# MicroController.net
KiCad netlist of a schematic drawn in Altium Designer
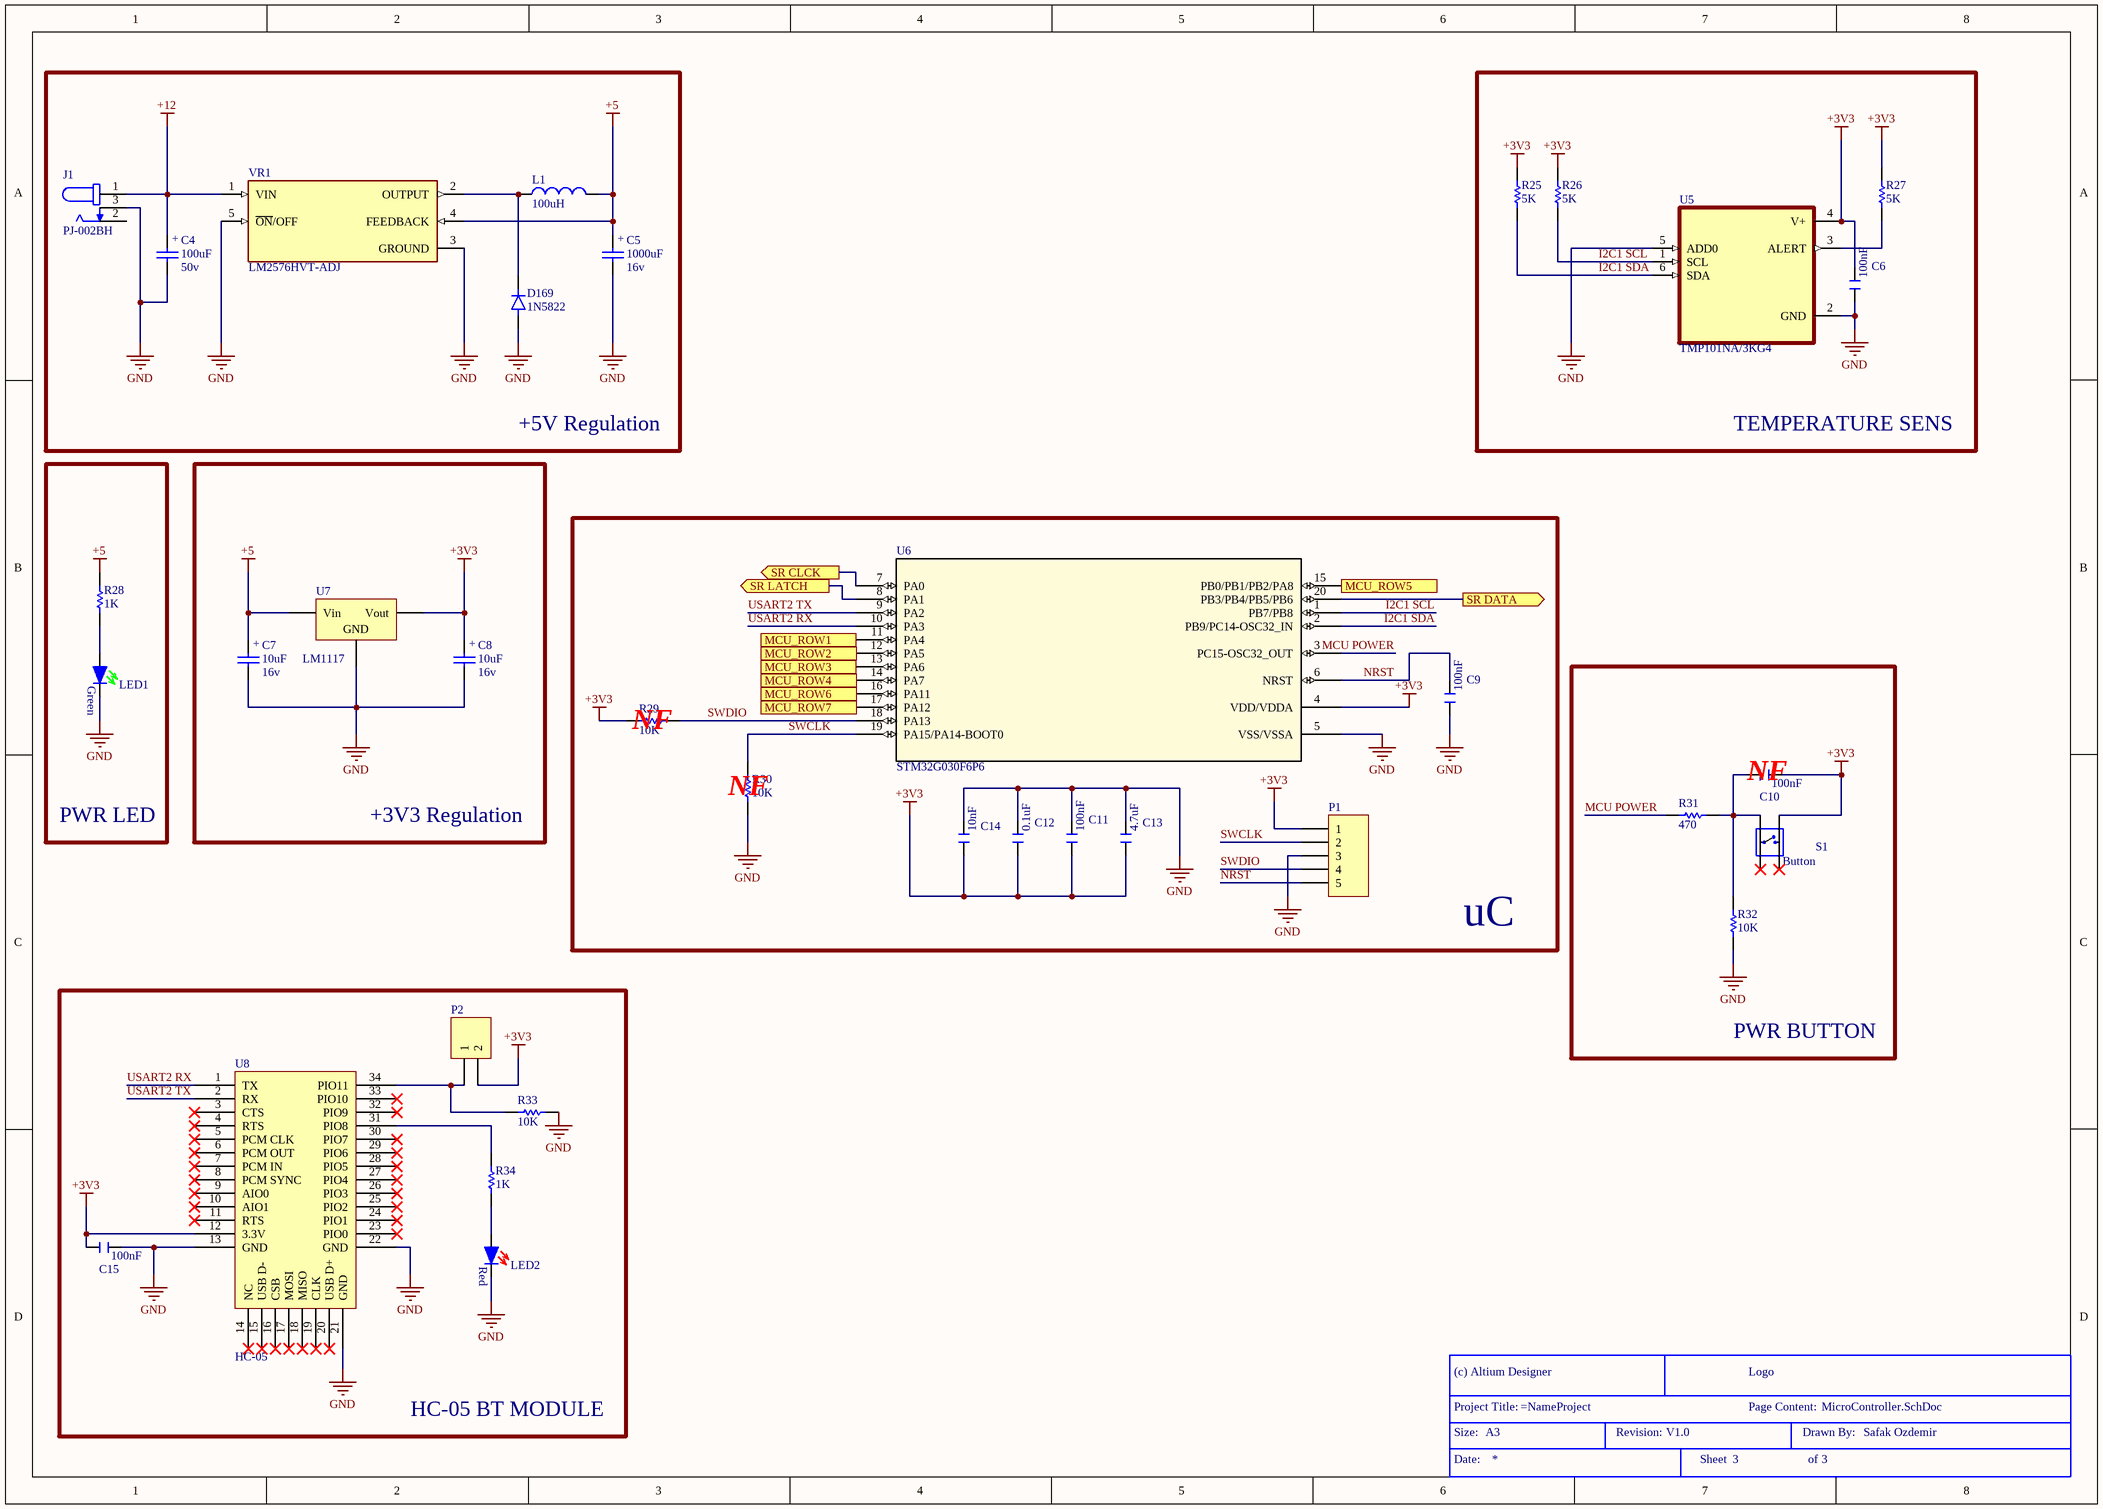
[diagram p0: MicroController.SchDoc]

(export (version "E")
  (design (tool "Eeschema 10.0.6"))
  (components
    (comp (ref "*")
      (value "Title Block")
      (fields (field (name "SIZE") "A3"))
      (libsource (lib "Bluetooth_Controlled_Led_Matrix_Design") (part "Title Block"))
    )
    (comp (ref "C4")
      (value "100uF")
      (footprint "MY_CLV_0810")
      (description "Polar capacitor")
      (fields (field (name "ASID PART NUMBER") "C-AS") (field (name "VOLTE") "50v"))
      (libsource (lib "Mylib") (part "Cap Pol"))
    )
    (comp (ref "C5")
      (value "1000uF")
      (footprint "MY_CLV_0810")
      (description "Polar capacitor")
      (fields (field (name "ASID PART NUMBER") "C-AS") (field (name "VOLTE") "16v"))
      (libsource (lib "Mylib") (part "Cap Pol"))
    )
    (comp (ref "C6")
      (value "CAP_0805_100nF")
      (footprint "CAP_0805")
      (description "0805 100nF 16VDC ±10% X7R")
      (fields
        (field (name "TOLERANCE") "%10")
        (field (name "MANUFACTURER") "https://www.ozdisan.com/Product/Detail/748339/CC0805KRX7R7BB104")
      )
      (libsource (lib "Bluetooth_Controlled_Led_Matrix_Design") (part "CAP_0805_100nF"))
    )
    (comp (ref "C7")
      (value "10uF")
      (footprint "MY_SMC_B")
      (description "Polar capacitor")
      (fields (field (name "ASID PART NUMBER") "C-AS") (field (name "VOLTE") "16v"))
      (libsource (lib "Mylib") (part "Cap Pol"))
    )
    (comp (ref "C8")
      (value "10uF")
      (footprint "MY_SMC_B")
      (description "Polar capacitor")
      (fields (field (name "ASID PART NUMBER") "C-AS") (field (name "VOLTE") "16v"))
      (libsource (lib "Mylib") (part "Cap Pol"))
    )
    (comp (ref "C9")
      (value "CAP_0805_100nF")
      (footprint "CAP_0805")
      (description "0805 100nF 16VDC ±10% X7R")
      (fields
        (field (name "TOLERANCE") "%10")
        (field (name "MANUFACTURER") "https://www.ozdisan.com/Product/Detail/748339/CC0805KRX7R7BB104")
      )
      (libsource (lib "Bluetooth_Controlled_Led_Matrix_Design") (part "CAP_0805_100nF"))
    )
    (comp (ref "C10")
      (value "CAP_0805_100nF")
      (footprint "CAP_0805")
      (description "0805 100nF 16VDC ±10% X7R")
      (fields
        (field (name "TOLERANCE") "%10")
        (field (name "MANUFACTURER") "https://www.ozdisan.com/Product/Detail/748339/CC0805KRX7R7BB104")
      )
      (libsource (lib "Bluetooth_Controlled_Led_Matrix_Design") (part "CAP_0805_100nF"))
    )
    (comp (ref "C11")
      (value "CAP_0805_100nF")
      (footprint "CAP_0805")
      (description "0805 100nF 16VDC ±10% X7R")
      (fields
        (field (name "TOLERANCE") "%10")
        (field (name "MANUFACTURER") "https://www.ozdisan.com/Product/Detail/748339/CC0805KRX7R7BB104")
      )
      (libsource (lib "Bluetooth_Controlled_Led_Matrix_Design") (part "CAP_0805_100nF"))
    )
    (comp (ref "C12")
      (value "CAP_0805_0.1uF")
      (footprint "CAP_0805")
      (description "0805 0.1uF 16VDC ±10% X7R")
      (fields
        (field (name "TOLERANCE") "%10")
        (field (name "MANUFACTURER") "https://www.ozdisan.com/Product/Detail/748339/CC0805KRX7R7BB104")
      )
      (libsource (lib "Bluetooth_Controlled_Led_Matrix_Design") (part "CAP_0805_0.1uF"))
    )
    (comp (ref "C13")
      (value "CAP_0805_4.7uF")
      (footprint "CAP_0805")
      (description "0805 4.7uF 16VDC ±10% X7R")
      (fields
        (field (name "TOLERANCE") "%10")
        (field (name "MANUFACTURER") "https://www.ozdisan.com/Product/Detail/748339/CC0805KRX7R7BB104")
      )
      (libsource (lib "Bluetooth_Controlled_Led_Matrix_Design") (part "CAP_0805_4.7uF"))
    )
    (comp (ref "C14")
      (value "CAP_0805_10nF")
      (footprint "CAP_0805")
      (description "0805 10nF 16VDC ±10% X7R")
      (fields
        (field (name "TOLERANCE") "%10")
        (field (name "MANUFACTURER") "https://www.ozdisan.com/Product/Detail/748339/CC0805KRX7R7BB104")
      )
      (libsource (lib "Bluetooth_Controlled_Led_Matrix_Design") (part "CAP_0805_10nF"))
    )
    (comp (ref "C15")
      (value "CAP_0805_100nF")
      (footprint "CAP_0805")
      (description "0805 100nF 16VDC ±10% X7R")
      (fields
        (field (name "TOLERANCE") "%10")
        (field (name "MANUFACTURER") "https://www.ozdisan.com/Product/Detail/748339/CC0805KRX7R7BB104")
      )
      (libsource (lib "Bluetooth_Controlled_Led_Matrix_Design") (part "CAP_0805_100nF"))
    )
    (comp (ref "D169")
      (value "1N5822")
      (footprint "DIOAD1990W125L900D530")
      (description "Diode Schottky 40 V 3A Through Hole DO-201AD")
      (fields (field (name "MF") "Micro Commercial"))
      (libsource (lib "Bluetooth_Controlled_Led_Matrix_Design") (part "1N5822"))
    )
    (comp (ref "J1")
      (value "PJ-002BH")
      (footprint "CUI_PJ-002BH")
      (description "2.5 x 6.5 mm, 5.0 A, Horizontal, Through Hole, Dc Power Jack Connector")
      (fields (field (name "MF") "CUI Devices"))
      (libsource (lib "Bluetooth_Controlled_Led_Matrix_Design") (part "PJ-002BH"))
    )
    (comp (ref "L1")
      (value "100uH")
      (footprint "MY_DR125")
      (description "Inductor")
      (fields (field (name "ASID PART NUMBER") "Inductor-AS"))
      (libsource (lib "Mylib") (part "Inductor"))
    )
    (comp (ref "LED1")
      (value "LED SMD 0805 GREEN")
      (footprint "LED_0805")
      (description "LED SMD 0805 GREEN 550mcd")
      (libsource (lib "Bluetooth_Controlled_Led_Matrix_Design") (part "LED_0805_GREEN"))
    )
    (comp (ref "LED2")
      (value "LED SMD 0805 RED")
      (footprint "LED_0805")
      (description "LED SMD 0805 RED 550mcd")
      (libsource (lib "Bluetooth_Controlled_Led_Matrix_Design") (part "LED_0805_RED"))
    )
    (comp (ref "P1")
      (value "Header 5")
      (footprint "My_1X05")
      (description "Header, 5-Pin")
      (fields (field (name "ASID PART NUMBER") "Header 5-AS"))
      (libsource (lib "Mylib") (part "Header 5"))
    )
    (comp (ref "P2")
      (value "Header 2")
      (footprint "My_1X02")
      (description "Header, 2-Pin")
      (fields (field (name "ASID PART NUMBER") "Header 2-AS"))
      (libsource (lib "Mylib") (part "Header 2"))
    )
    (comp (ref "R25")
      (value "5K")
      (footprint "MY_0805")
      (description "Standard resistor")
      (fields (field (name "ASID PART NUMBER") "Res-AS"))
      (libsource (lib "Mylib") (part "Res"))
    )
    (comp (ref "R26")
      (value "5K")
      (footprint "MY_0805")
      (description "Standard resistor")
      (fields (field (name "ASID PART NUMBER") "Res-AS"))
      (libsource (lib "Mylib") (part "Res"))
    )
    (comp (ref "R27")
      (value "5K")
      (footprint "MY_0805")
      (description "Standard resistor")
      (fields (field (name "ASID PART NUMBER") "Res-AS"))
      (libsource (lib "Mylib") (part "Res"))
    )
    (comp (ref "R28")
      (value "1K")
      (footprint "MY_0805")
      (description "Standard resistor")
      (fields (field (name "ASID PART NUMBER") "Res-AS"))
      (libsource (lib "Mylib") (part "Res"))
    )
    (comp (ref "R29")
      (value "10K")
      (footprint "MY_0805")
      (description "Standard resistor")
      (fields (field (name "ASID PART NUMBER") "Res-AS"))
      (libsource (lib "Mylib") (part "Res"))
    )
    (comp (ref "R30")
      (value "10K")
      (footprint "MY_0805")
      (description "Standard resistor")
      (fields (field (name "ASID PART NUMBER") "Res-AS"))
      (libsource (lib "Mylib") (part "Res"))
    )
    (comp (ref "R31")
      (value "470")
      (footprint "MY_0805")
      (description "Standard resistor")
      (fields (field (name "ASID PART NUMBER") "Res-AS"))
      (libsource (lib "Mylib") (part "Res"))
    )
    (comp (ref "R32")
      (value "10K")
      (footprint "MY_0805")
      (description "Standard resistor")
      (fields (field (name "ASID PART NUMBER") "Res-AS"))
      (libsource (lib "Mylib") (part "Res"))
    )
    (comp (ref "R33")
      (value "10K")
      (footprint "MY_0805")
      (description "Standard resistor")
      (fields (field (name "ASID PART NUMBER") "Res-AS"))
      (libsource (lib "Mylib") (part "Res"))
    )
    (comp (ref "R34")
      (value "1K")
      (footprint "MY_0805")
      (description "Standard resistor")
      (fields (field (name "ASID PART NUMBER") "Res-AS"))
      (libsource (lib "Mylib") (part "Res"))
    )
    (comp (ref "S1")
      (value "6MM_BUTTON")
      (footprint "6MM_TACTILE_SWITCH")
      (description "TACT 6x6MM 11MM 250gf SMD")
      (libsource (lib "Bluetooth_Controlled_Led_Matrix_Design") (part "6MM_BUTTON"))
    )
    (comp (ref "U5")
      (value "TMP101NA/3KG4")
      (footprint "SOT95P280X145-6N")
      (libsource (lib "Bluetooth_Controlled_Led_Matrix_Design") (part "TMP101NA/3KG4"))
    )
    (comp (ref "U6")
      (value "STM32G030F6P6")
      (footprint "TSSOP20")
      (description "No Description Available")
      (libsource (lib "Bluetooth_Controlled_Led_Matrix_Design") (part "STM32G030F6P6"))
    )
    (comp (ref "U7")
      (value "LM1117")
      (footprint "MY_SOT223")
      (description "Low Drop Voltage Reg")
      (fields (field (name "ASID PART NUMBER") "LM1117-AS"))
      (libsource (lib "Mylib") (part "LM1117"))
    )
    (comp (ref "U8")
      (value "HC-05")
      (footprint "HC-05")
      (libsource (lib "Bluetooth_Controlled_Led_Matrix_Design") (part "HC-05"))
    )
    (comp (ref "VR1")
      (value "LM2576HVT-ADJ")
      (footprint "TO170P1067X483X1651-5")
      (description "SIMPLE SWITCHER&reg; 4V to 60V, 3A Low Component Count Step-Down Regulator 5-TO-220 -40 to 125")
      (fields (field (name "MF") "Texas Instruments"))
      (libsource (lib "Bluetooth_Controlled_Led_Matrix_Design") (part "LM2576HVT-ADJ"))
    )
  )
  (nets
    (net (code "1") (name "+3V3") (class "Default")
      (node (ref "C10") (pin "2") (pinfunction "2_2") (pintype "passive"))
      (node (ref "C11") (pin "1") (pinfunction "1_1") (pintype "passive"))
      (node (ref "C12") (pin "1") (pinfunction "1_1") (pintype "passive"))
      (node (ref "C13") (pin "1") (pinfunction "1_1") (pintype "passive"))
      (node (ref "C14") (pin "1") (pinfunction "1_1") (pintype "passive"))
      (node (ref "C15") (pin "1") (pinfunction "1_1") (pintype "passive"))
      (node (ref "C6") (pin "2") (pinfunction "2_2") (pintype "passive"))
      (node (ref "C8") (pin "+") (pinfunction "+_+") (pintype "passive"))
      (node (ref "P1") (pin "1") (pinfunction "1_1") (pintype "passive"))
      (node (ref "P2") (pin "2") (pinfunction "2_2") (pintype "passive"))
      (node (ref "R25") (pin "1") (pinfunction "1_1") (pintype "passive"))
      (node (ref "R26") (pin "1") (pinfunction "1_1") (pintype "passive"))
      (node (ref "R27") (pin "1") (pinfunction "1_1") (pintype "passive"))
      (node (ref "R29") (pin "1") (pinfunction "1_1") (pintype "passive"))
      (node (ref "S1") (pin "4") (pinfunction "4_4") (pintype "passive"))
      (node (ref "U5") (pin "4") (pinfunction "V+_4") (pintype "power_in"))
      (node (ref "U6") (pin "4") (pinfunction "VDD/VDDA_4") (pintype "power_in"))
      (node (ref "U7") (pin "2") (pinfunction "Vout_2") (pintype "passive"))
      (node (ref "U8") (pin "12") (pinfunction "3.3V_12") (pintype "passive"))
    )
    (net (code "2") (name "+5") (class "Default")
      (node (ref "C5") (pin "+") (pinfunction "+_+") (pintype "passive"))
      (node (ref "C7") (pin "+") (pinfunction "+_+") (pintype "passive"))
      (node (ref "L1") (pin "2") (pinfunction "2_2") (pintype "passive"))
      (node (ref "R28") (pin "1") (pinfunction "1_1") (pintype "passive"))
      (node (ref "U7") (pin "3") (pinfunction "Vin_3") (pintype "passive"))
      (node (ref "VR1") (pin "4") (pinfunction "FEEDBACK_4") (pintype "input"))
    )
    (net (code "3") (name "+12") (class "Default")
      (node (ref "C4") (pin "+") (pinfunction "+_+") (pintype "passive"))
      (node (ref "J1") (pin "1") (pinfunction "1_1") (pintype "passive"))
      (node (ref "VR1") (pin "1") (pinfunction "VIN_1") (pintype "input"))
    )
    (net (code "4") (name "/I2C1 SCL") (class "Default")
      (node (ref "R26") (pin "2") (pinfunction "2_2") (pintype "passive"))
      (node (ref "U5") (pin "1") (pinfunction "SCL_1") (pintype "input"))
      (node (ref "U6") (pin "1") (pinfunction "PB7/PB8_1") (pintype "bidirectional"))
    )
    (net (code "5") (name "/I2C1 SDA") (class "Default")
      (node (ref "R25") (pin "2") (pinfunction "2_2") (pintype "passive"))
      (node (ref "U5") (pin "6") (pinfunction "SDA_6") (pintype "input"))
      (node (ref "U6") (pin "2") (pinfunction "PB9/PC14-OSC32_IN_2") (pintype "bidirectional"))
    )
    (net (code "6") (name "/MCU POWER") (class "Default")
      (node (ref "R31") (pin "1") (pinfunction "1_1") (pintype "passive"))
      (node (ref "U6") (pin "3") (pinfunction "PC15-OSC32_OUT_3") (pintype "bidirectional"))
    )
    (net (code "7") (name "/MCU_ROW1") (class "Default")
      (node (ref "U6") (pin "11") (pinfunction "PA4_11") (pintype "bidirectional"))
    )
    (net (code "8") (name "/MCU_ROW2") (class "Default")
      (node (ref "U6") (pin "12") (pinfunction "PA5_12") (pintype "bidirectional"))
    )
    (net (code "9") (name "/MCU_ROW3") (class "Default")
      (node (ref "U6") (pin "13") (pinfunction "PA6_13") (pintype "bidirectional"))
    )
    (net (code "10") (name "/MCU_ROW4") (class "Default")
      (node (ref "U6") (pin "14") (pinfunction "PA7_14") (pintype "bidirectional"))
    )
    (net (code "11") (name "/MCU_ROW5") (class "Default")
      (node (ref "U6") (pin "15") (pinfunction "PB0/PB1/PB2/PA8_15") (pintype "bidirectional"))
    )
    (net (code "12") (name "/MCU_ROW6") (class "Default")
      (node (ref "U6") (pin "16") (pinfunction "PA11_16") (pintype "bidirectional"))
    )
    (net (code "13") (name "/MCU_ROW7") (class "Default")
      (node (ref "U6") (pin "17") (pinfunction "PA12_17") (pintype "bidirectional"))
    )
    (net (code "14") (name "/NRST") (class "Default")
      (node (ref "C9") (pin "2") (pinfunction "2_2") (pintype "passive"))
      (node (ref "P1") (pin "5") (pinfunction "5_5") (pintype "passive"))
      (node (ref "U6") (pin "6") (pinfunction "NRST_6") (pintype "bidirectional"))
    )
    (net (code "15") (name "/SR CLCK") (class "Default")
      (node (ref "U6") (pin "7") (pinfunction "PA0_7") (pintype "bidirectional"))
    )
    (net (code "16") (name "/SR DATA") (class "Default")
      (node (ref "U6") (pin "20") (pinfunction "PB3/PB4/PB5/PB6_20") (pintype "bidirectional"))
    )
    (net (code "17") (name "/SR LATCH") (class "Default")
      (node (ref "U6") (pin "8") (pinfunction "PA1_8") (pintype "bidirectional"))
    )
    (net (code "18") (name "/SWCLK") (class "Default")
      (node (ref "P1") (pin "2") (pinfunction "2_2") (pintype "passive"))
      (node (ref "R30") (pin "1") (pinfunction "1_1") (pintype "passive"))
      (node (ref "U6") (pin "19") (pinfunction "PA15/PA14-BOOT0_19") (pintype "bidirectional"))
    )
    (net (code "19") (name "/SWDIO") (class "Default")
      (node (ref "P1") (pin "4") (pinfunction "4_4") (pintype "passive"))
      (node (ref "R29") (pin "2") (pinfunction "2_2") (pintype "passive"))
      (node (ref "U6") (pin "18") (pinfunction "PA13_18") (pintype "bidirectional"))
    )
    (net (code "20") (name "/USART2 RX") (class "Default")
      (node (ref "U6") (pin "10") (pinfunction "PA3_10") (pintype "bidirectional"))
      (node (ref "U8") (pin "1") (pinfunction "TX_1") (pintype "passive"))
    )
    (net (code "21") (name "/USART2 TX") (class "Default")
      (node (ref "U6") (pin "9") (pinfunction "PA2_9") (pintype "bidirectional"))
      (node (ref "U8") (pin "2") (pinfunction "RX_2") (pintype "passive"))
    )
    (net (code "22") (name "GND") (class "Default")
      (node (ref "C11") (pin "2") (pinfunction "2_2") (pintype "passive"))
      (node (ref "C12") (pin "2") (pinfunction "2_2") (pintype "passive"))
      (node (ref "C13") (pin "2") (pinfunction "2_2") (pintype "passive"))
      (node (ref "C14") (pin "2") (pinfunction "2_2") (pintype "passive"))
      (node (ref "C15") (pin "2") (pinfunction "2_2") (pintype "passive"))
      (node (ref "C4") (pin "-") (pinfunction "-_-") (pintype "passive"))
      (node (ref "C5") (pin "-") (pinfunction "-_-") (pintype "passive"))
      (node (ref "C6") (pin "1") (pinfunction "1_1") (pintype "passive"))
      (node (ref "C7") (pin "-") (pinfunction "-_-") (pintype "passive"))
      (node (ref "C8") (pin "-") (pinfunction "-_-") (pintype "passive"))
      (node (ref "C9") (pin "1") (pinfunction "1_1") (pintype "passive"))
      (node (ref "D169") (pin "A") (pinfunction "A_A") (pintype "passive"))
      (node (ref "J1") (pin "3") (pinfunction "3_3") (pintype "passive"))
      (node (ref "LED1") (pin "C") (pinfunction "C_C") (pintype "passive"))
      (node (ref "LED2") (pin "C") (pinfunction "C_C") (pintype "passive"))
      (node (ref "P1") (pin "3") (pinfunction "3_3") (pintype "passive"))
      (node (ref "R30") (pin "2") (pinfunction "2_2") (pintype "passive"))
      (node (ref "R32") (pin "2") (pinfunction "2_2") (pintype "passive"))
      (node (ref "R33") (pin "2") (pinfunction "2_2") (pintype "passive"))
      (node (ref "U5") (pin "2") (pinfunction "GND_2") (pintype "power_in"))
      (node (ref "U5") (pin "5") (pinfunction "ADD0_5") (pintype "input"))
      (node (ref "U6") (pin "5") (pinfunction "VSS/VSSA_5") (pintype "power_in"))
      (node (ref "U7") (pin "1") (pinfunction "GND_1") (pintype "passive"))
      (node (ref "U8") (pin "13") (pinfunction "GND_13") (pintype "passive"))
      (node (ref "U8") (pin "21") (pinfunction "GND_21") (pintype "passive"))
      (node (ref "U8") (pin "22") (pinfunction "GND_22") (pintype "passive"))
      (node (ref "VR1") (pin "3") (pinfunction "GROUND_3") (pintype "power_in"))
      (node (ref "VR1") (pin "5") (pinfunction "~{ON}/OFF_5") (pintype "input"))
    )
    (net (code "23") (name "Net-(C10-Pad1)") (class "Default")
      (node (ref "C10") (pin "1") (pinfunction "1_1") (pintype "passive"))
      (node (ref "R31") (pin "2") (pinfunction "2_2") (pintype "passive"))
      (node (ref "R32") (pin "1") (pinfunction "1_1") (pintype "passive"))
      (node (ref "S1") (pin "3") (pinfunction "3_3") (pintype "passive"))
    )
    (net (code "24") (name "Net-(D169-K)") (class "Default")
      (node (ref "D169") (pin "C") (pinfunction "K_C") (pintype "passive"))
      (node (ref "L1") (pin "1") (pinfunction "1_1") (pintype "passive"))
      (node (ref "VR1") (pin "2") (pinfunction "OUTPUT_2") (pintype "output"))
    )
    (net (code "25") (name "Net-(LED1-PadA)") (class "Default")
      (node (ref "LED1") (pin "A") (pinfunction "A_A") (pintype "passive"))
      (node (ref "R28") (pin "2") (pinfunction "2_2") (pintype "passive"))
    )
    (net (code "26") (name "Net-(LED2-PadA)") (class "Default")
      (node (ref "LED2") (pin "A") (pinfunction "A_A") (pintype "passive"))
      (node (ref "R34") (pin "2") (pinfunction "2_2") (pintype "passive"))
    )
    (net (code "27") (name "Net-(U5-ALERT)") (class "Default")
      (node (ref "R27") (pin "2") (pinfunction "2_2") (pintype "passive"))
      (node (ref "U5") (pin "3") (pinfunction "ALERT_3") (pintype "output"))
    )
    (net (code "28") (name "Net-(U8-PIO8)") (class "Default")
      (node (ref "R34") (pin "1") (pinfunction "1_1") (pintype "passive"))
      (node (ref "U8") (pin "31") (pinfunction "PIO8_31") (pintype "passive"))
    )
    (net (code "29") (name "Net-(U8-PIO11)") (class "Default")
      (node (ref "P2") (pin "1") (pinfunction "1_1") (pintype "passive"))
      (node (ref "R33") (pin "1") (pinfunction "1_1") (pintype "passive"))
      (node (ref "U8") (pin "34") (pinfunction "PIO11_34") (pintype "passive"))
    )
    (net (code "30") (name "unconnected-(J1-Pad2)") (class "Default")
      (node (ref "J1") (pin "2") (pinfunction "2_2") (pintype "passive"))
    )
    (net (code "31") (name "unconnected-(S1-Pad1)") (class "Default")
      (node (ref "S1") (pin "1") (pinfunction "1_1") (pintype "passive+no_connect"))
    )
    (net (code "32") (name "unconnected-(S1-Pad2)") (class "Default")
      (node (ref "S1") (pin "2") (pinfunction "2_2") (pintype "passive+no_connect"))
    )
    (net (code "33") (name "unconnected-(U8-AIO0-Pad9)") (class "Default")
      (node (ref "U8") (pin "9") (pinfunction "AIO0_9") (pintype "passive+no_connect"))
    )
    (net (code "34") (name "unconnected-(U8-AIO1-Pad10)") (class "Default")
      (node (ref "U8") (pin "10") (pinfunction "AIO1_10") (pintype "passive+no_connect"))
    )
    (net (code "35") (name "unconnected-(U8-CLK-Pad19)") (class "Default")
      (node (ref "U8") (pin "19") (pinfunction "CLK_19") (pintype "passive+no_connect"))
    )
    (net (code "36") (name "unconnected-(U8-CSB-Pad16)") (class "Default")
      (node (ref "U8") (pin "16") (pinfunction "CSB_16") (pintype "passive+no_connect"))
    )
    (net (code "37") (name "unconnected-(U8-CTS-Pad3)") (class "Default")
      (node (ref "U8") (pin "3") (pinfunction "CTS_3") (pintype "passive+no_connect"))
    )
    (net (code "38") (name "unconnected-(U8-MISO-Pad18)") (class "Default")
      (node (ref "U8") (pin "18") (pinfunction "MISO_18") (pintype "passive+no_connect"))
    )
    (net (code "39") (name "unconnected-(U8-MOSI-Pad17)") (class "Default")
      (node (ref "U8") (pin "17") (pinfunction "MOSI_17") (pintype "passive+no_connect"))
    )
    (net (code "40") (name "unconnected-(U8-NC-Pad14)") (class "Default")
      (node (ref "U8") (pin "14") (pinfunction "NC_14") (pintype "passive+no_connect"))
    )
    (net (code "41") (name "unconnected-(U8-PCM_CLK-Pad5)") (class "Default")
      (node (ref "U8") (pin "5") (pinfunction "PCM_CLK_5") (pintype "passive+no_connect"))
    )
    (net (code "42") (name "unconnected-(U8-PCM_IN-Pad7)") (class "Default")
      (node (ref "U8") (pin "7") (pinfunction "PCM_IN_7") (pintype "passive+no_connect"))
    )
    (net (code "43") (name "unconnected-(U8-PCM_OUT-Pad6)") (class "Default")
      (node (ref "U8") (pin "6") (pinfunction "PCM_OUT_6") (pintype "passive+no_connect"))
    )
    (net (code "44") (name "unconnected-(U8-PCM_SYNC-Pad8)") (class "Default")
      (node (ref "U8") (pin "8") (pinfunction "PCM_SYNC_8") (pintype "passive+no_connect"))
    )
    (net (code "45") (name "unconnected-(U8-PIO0-Pad23)") (class "Default")
      (node (ref "U8") (pin "23") (pinfunction "PIO0_23") (pintype "passive+no_connect"))
    )
    (net (code "46") (name "unconnected-(U8-PIO1-Pad24)") (class "Default")
      (node (ref "U8") (pin "24") (pinfunction "PIO1_24") (pintype "passive+no_connect"))
    )
    (net (code "47") (name "unconnected-(U8-PIO2-Pad25)") (class "Default")
      (node (ref "U8") (pin "25") (pinfunction "PIO2_25") (pintype "passive+no_connect"))
    )
    (net (code "48") (name "unconnected-(U8-PIO3-Pad26)") (class "Default")
      (node (ref "U8") (pin "26") (pinfunction "PIO3_26") (pintype "passive+no_connect"))
    )
    (net (code "49") (name "unconnected-(U8-PIO4-Pad27)") (class "Default")
      (node (ref "U8") (pin "27") (pinfunction "PIO4_27") (pintype "passive+no_connect"))
    )
    (net (code "50") (name "unconnected-(U8-PIO5-Pad28)") (class "Default")
      (node (ref "U8") (pin "28") (pinfunction "PIO5_28") (pintype "passive+no_connect"))
    )
    (net (code "51") (name "unconnected-(U8-PIO6-Pad29)") (class "Default")
      (node (ref "U8") (pin "29") (pinfunction "PIO6_29") (pintype "passive+no_connect"))
    )
    (net (code "52") (name "unconnected-(U8-PIO7-Pad30)") (class "Default")
      (node (ref "U8") (pin "30") (pinfunction "PIO7_30") (pintype "passive+no_connect"))
    )
    (net (code "53") (name "unconnected-(U8-PIO9-Pad32)") (class "Default")
      (node (ref "U8") (pin "32") (pinfunction "PIO9_32") (pintype "passive+no_connect"))
    )
    (net (code "54") (name "unconnected-(U8-PIO10-Pad33)") (class "Default")
      (node (ref "U8") (pin "33") (pinfunction "PIO10_33") (pintype "passive+no_connect"))
    )
    (net (code "55") (name "unconnected-(U8-RTS-Pad4)") (class "Default")
      (node (ref "U8") (pin "4") (pinfunction "RTS_4") (pintype "passive+no_connect"))
    )
    (net (code "56") (name "unconnected-(U8-RTS-Pad11)") (class "Default")
      (node (ref "U8") (pin "11") (pinfunction "RTS_11") (pintype "passive+no_connect"))
    )
    (net (code "57") (name "unconnected-(U8-USB_D+-Pad20)") (class "Default")
      (node (ref "U8") (pin "20") (pinfunction "USB_D+_20") (pintype "passive+no_connect"))
    )
    (net (code "58") (name "unconnected-(U8-USB_D--Pad15)") (class "Default")
      (node (ref "U8") (pin "15") (pinfunction "USB_D-_15") (pintype "passive+no_connect"))
    )
  )
)
